# TX_Balun.net
KiCad netlist of a schematic drawn in Altium Designer
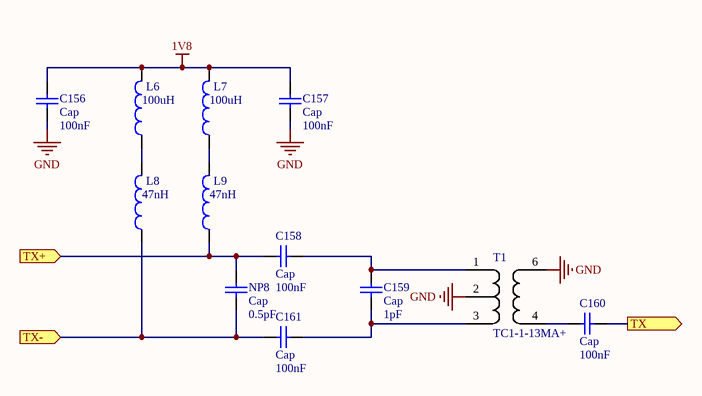
[diagram p0: TX Balun.SchDoc]

(export (version "E")
  (design (tool "Eeschema 10.0.6"))
  (components
    (comp (ref "C156")
      (value "Cap")
      (footprint "0402-A")
      (description "Capacitor")
      (fields (field (name "ALTIUM_VALUE") "100nF") (field (name "PUBLISHER") "Altium Limited"))
      (libsource (lib "Miscellaneous Devices") (part "Cap"))
    )
    (comp (ref "C157")
      (value "Cap")
      (footprint "0402-A")
      (description "Capacitor")
      (fields (field (name "ALTIUM_VALUE") "100nF") (field (name "PUBLISHER") "Altium Limited"))
      (libsource (lib "Miscellaneous Devices") (part "Cap"))
    )
    (comp (ref "C158")
      (value "Cap")
      (footprint "0402-A")
      (description "Capacitor")
      (fields (field (name "ALTIUM_VALUE") "100nF") (field (name "PUBLISHER") "Altium Limited"))
      (libsource (lib "Miscellaneous Devices") (part "Cap"))
    )
    (comp (ref "C159")
      (value "Cap")
      (footprint "0402-A")
      (description "Capacitor")
      (fields (field (name "ALTIUM_VALUE") "1pF") (field (name "PUBLISHER") "Altium Limited"))
      (libsource (lib "Miscellaneous Devices") (part "Cap"))
    )
    (comp (ref "C160")
      (value "Cap")
      (footprint "0402-A")
      (description "Capacitor")
      (fields (field (name "ALTIUM_VALUE") "100nF") (field (name "PUBLISHER") "Altium Limited"))
      (libsource (lib "Miscellaneous Devices") (part "Cap"))
    )
    (comp (ref "C161")
      (value "Cap")
      (footprint "0402-A")
      (description "Capacitor")
      (fields (field (name "ALTIUM_VALUE") "100nF") (field (name "PUBLISHER") "Altium Limited"))
      (libsource (lib "Miscellaneous Devices") (part "Cap"))
    )
    (comp (ref "L6")
      (value "100uH")
      (footprint "6-0805_M")
      (description "Inductor")
      (fields (field (name "PUBLISHER") "Altium Limited"))
      (libsource (lib "Miscellaneous Devices") (part "Inductor"))
    )
    (comp (ref "L7")
      (value "100uH")
      (footprint "6-0805_M")
      (description "Inductor")
      (fields (field (name "PUBLISHER") "Altium Limited"))
      (libsource (lib "Miscellaneous Devices") (part "Inductor"))
    )
    (comp (ref "L8")
      (value "47nH")
      (footprint "0402-A")
      (description "Inductor")
      (fields (field (name "PUBLISHER") "Altium Limited"))
      (libsource (lib "Miscellaneous Devices") (part "Inductor"))
    )
    (comp (ref "L9")
      (value "47nH")
      (footprint "0402-A")
      (description "Inductor")
      (fields (field (name "PUBLISHER") "Altium Limited"))
      (libsource (lib "Miscellaneous Devices") (part "Inductor"))
    )
    (comp (ref "NP8")
      (value "Cap")
      (footprint "0402-A")
      (description "Capacitor")
      (fields (field (name "ALTIUM_VALUE") "0.5pF") (field (name "PUBLISHER") "Altium Limited"))
      (libsource (lib "Miscellaneous Devices") (part "Cap"))
    )
    (comp (ref "T1")
      (value "TC1-1-13MA+")
      (footprint "TC1-1-13MA+")
      (libsource (lib "TC1-1-13MA+") (part "TC1-1-13MA+"))
    )
  )
  (nets
    (net (code "1") (name "/TX") (class "Default")
      (node (ref "C160") (pin "1") (pinfunction "1_1") (pintype "passive"))
    )
    (net (code "2") (name "/TX+") (class "Default")
      (node (ref "C158") (pin "2") (pinfunction "2_2") (pintype "passive"))
      (node (ref "L9") (pin "1") (pinfunction "1_1") (pintype "passive"))
      (node (ref "NP8") (pin "2") (pinfunction "2_2") (pintype "passive"))
    )
    (net (code "3") (name "/TX-") (class "Default")
      (node (ref "C161") (pin "2") (pinfunction "2_2") (pintype "passive"))
      (node (ref "L8") (pin "1") (pinfunction "1_1") (pintype "passive"))
      (node (ref "NP8") (pin "1") (pinfunction "1_1") (pintype "passive"))
    )
    (net (code "4") (name "1V8") (class "Default")
      (node (ref "C156") (pin "2") (pinfunction "2_2") (pintype "passive"))
      (node (ref "C157") (pin "2") (pinfunction "2_2") (pintype "passive"))
      (node (ref "L6") (pin "2") (pinfunction "2_2") (pintype "passive"))
      (node (ref "L7") (pin "2") (pinfunction "2_2") (pintype "passive"))
    )
    (net (code "5") (name "GND") (class "Default")
      (node (ref "C156") (pin "1") (pinfunction "1_1") (pintype "passive"))
      (node (ref "C157") (pin "1") (pinfunction "1_1") (pintype "passive"))
      (node (ref "T1") (pin "2") (pintype "passive"))
      (node (ref "T1") (pin "6") (pintype "passive"))
    )
    (net (code "6") (name "Net-(C158-Pad1)") (class "Default")
      (node (ref "C158") (pin "1") (pinfunction "1_1") (pintype "passive"))
      (node (ref "C159") (pin "2") (pinfunction "2_2") (pintype "passive"))
      (node (ref "T1") (pin "1") (pintype "passive"))
    )
    (net (code "7") (name "Net-(C159-Pad1)") (class "Default")
      (node (ref "C159") (pin "1") (pinfunction "1_1") (pintype "passive"))
      (node (ref "C161") (pin "1") (pinfunction "1_1") (pintype "passive"))
      (node (ref "T1") (pin "3") (pintype "passive"))
    )
    (net (code "8") (name "Net-(C160-Pad2)") (class "Default")
      (node (ref "C160") (pin "2") (pinfunction "2_2") (pintype "passive"))
      (node (ref "T1") (pin "4") (pintype "passive"))
    )
    (net (code "9") (name "Net-(L6-Pad1)") (class "Default")
      (node (ref "L6") (pin "1") (pinfunction "1_1") (pintype "passive"))
      (node (ref "L8") (pin "2") (pinfunction "2_2") (pintype "passive"))
    )
    (net (code "10") (name "Net-(L7-Pad1)") (class "Default")
      (node (ref "L7") (pin "1") (pinfunction "1_1") (pintype "passive"))
      (node (ref "L9") (pin "2") (pinfunction "2_2") (pintype "passive"))
    )
  )
)
